# Tesseract_Motherboard.net
KiCad netlist of a schematic drawn in EasyEDA
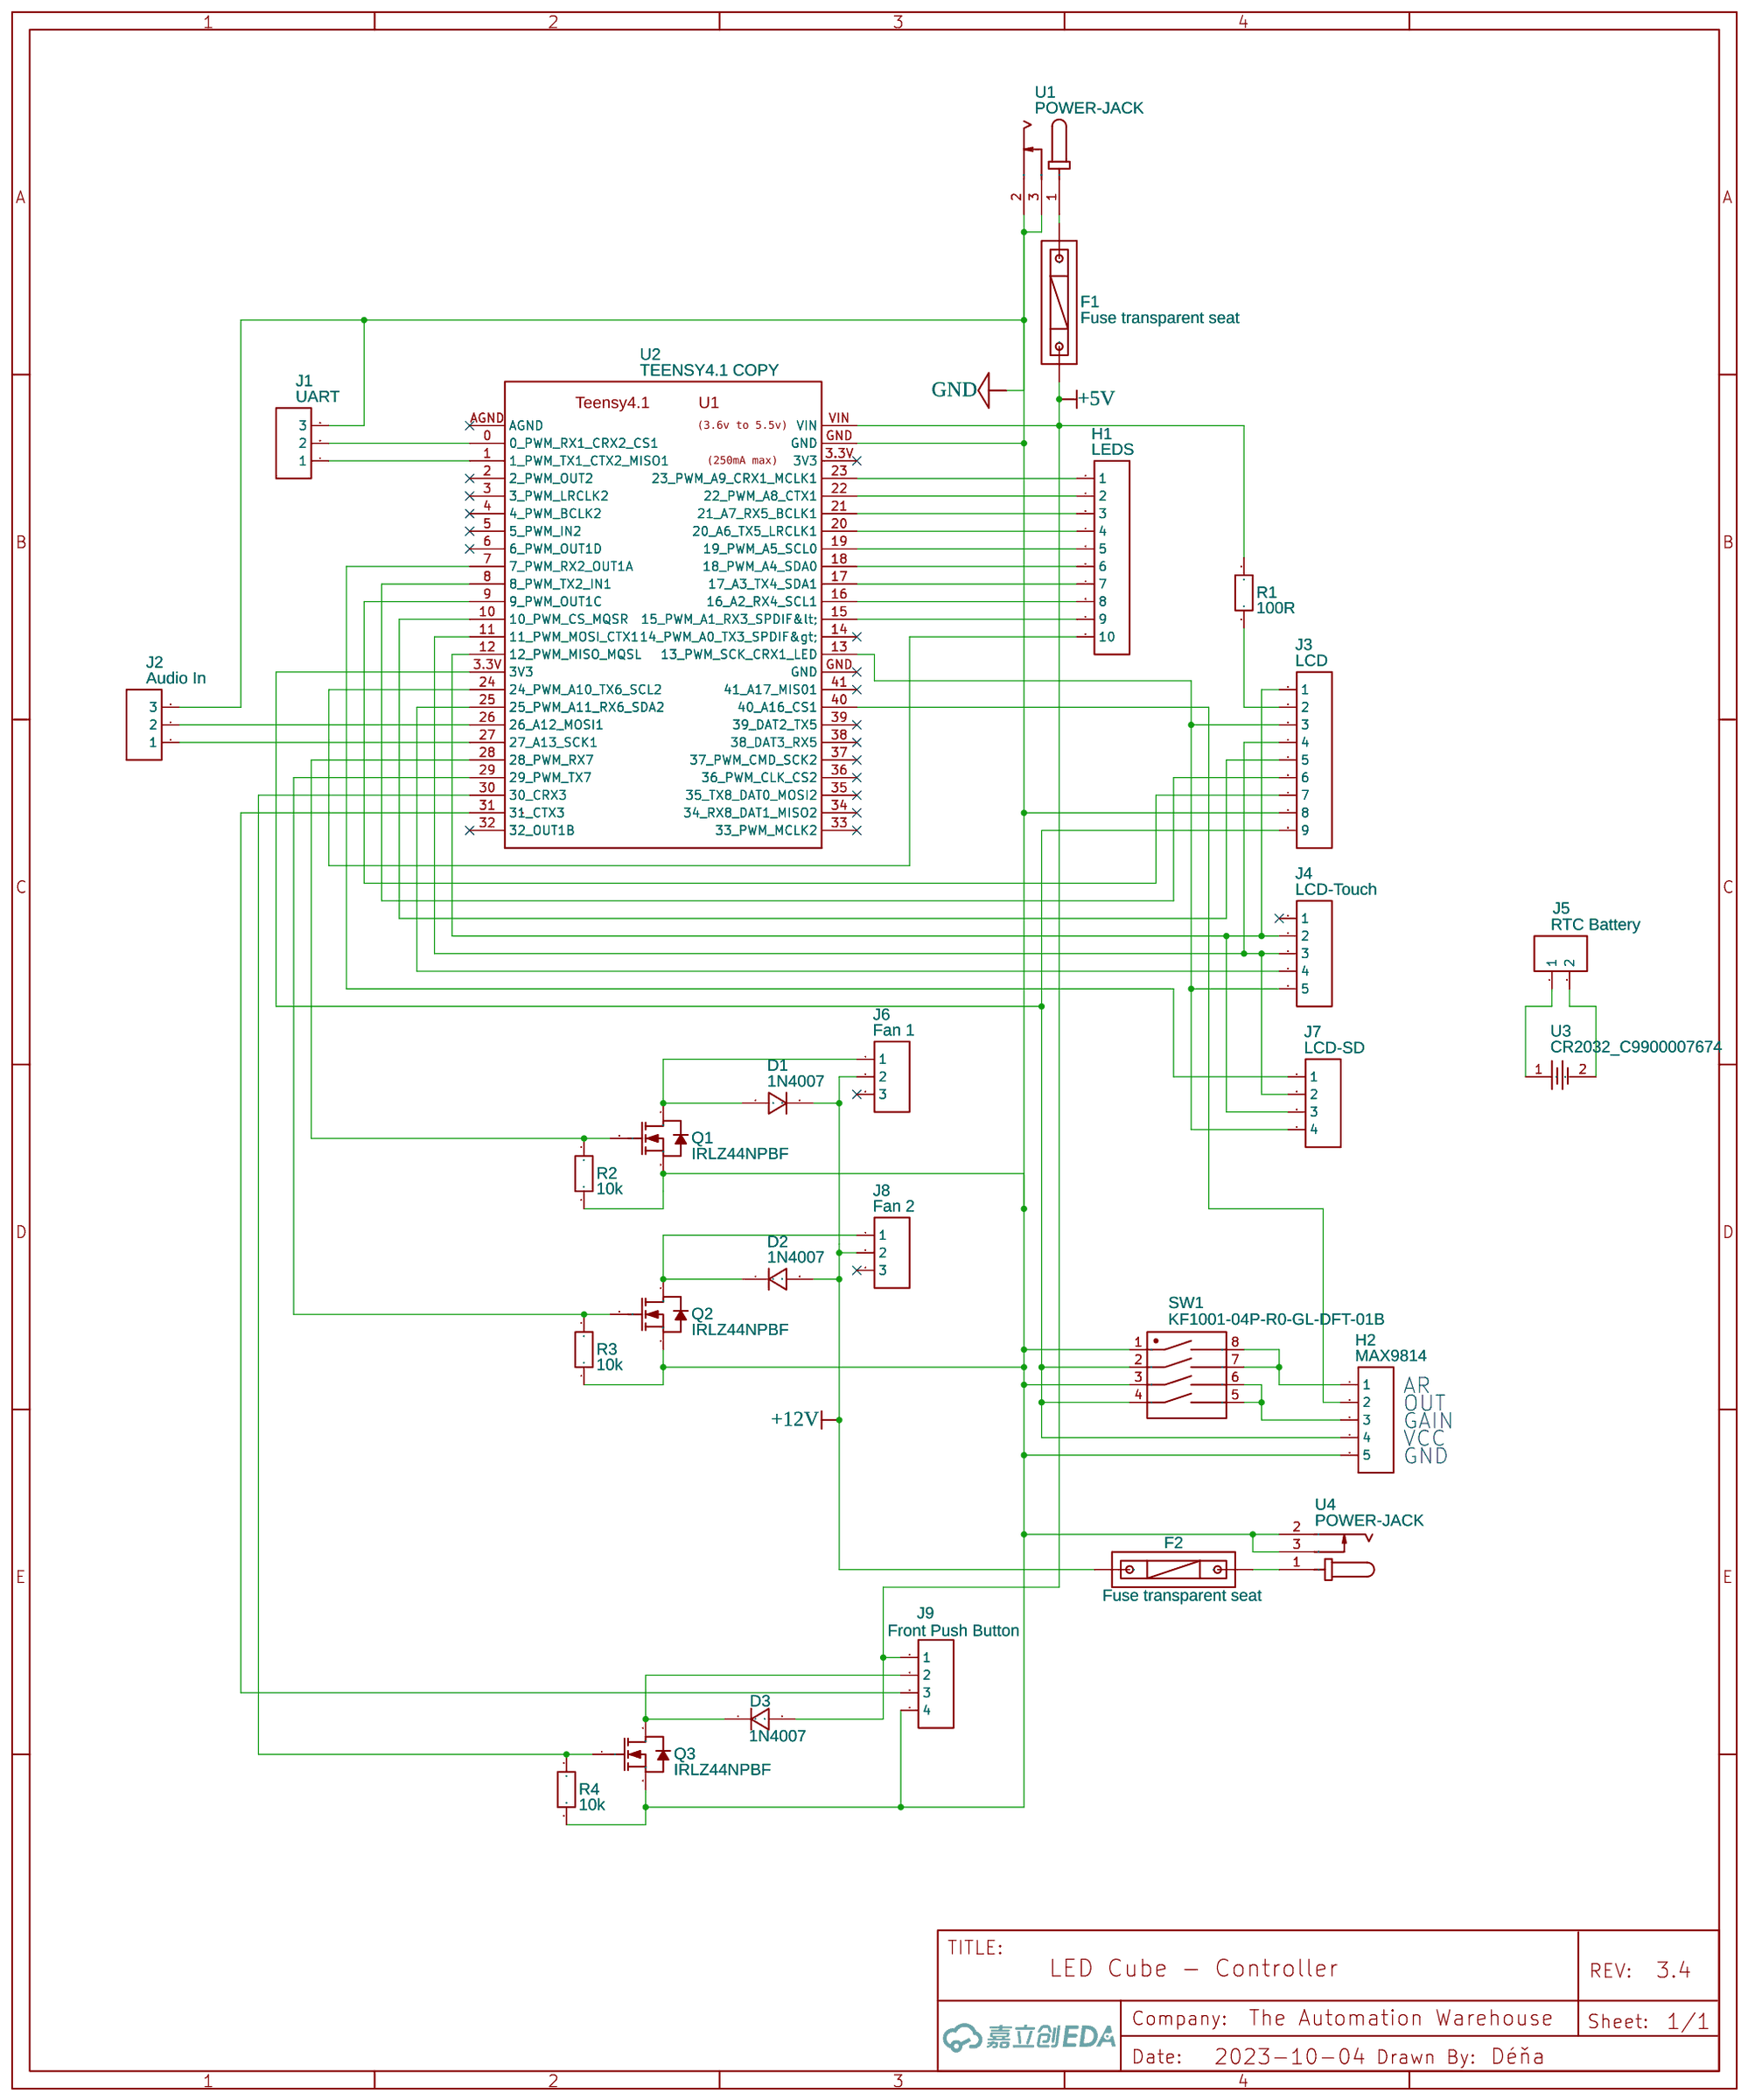
[diagram p0: schematic sheet]

(export (version "E")
  (design (tool "Eeschema 10.0.6"))
  (components
    (comp (ref "D1")
      (value "1N4007")
      (fields (field (name "BOM_Supplier Part") "C106903"))
      (libsource (lib "") (part "1N4007_1"))
    )
    (comp (ref "D2")
      (value "1N4007")
      (fields (field (name "BOM_Supplier Part") "C106903"))
      (libsource (lib "") (part "1N4007"))
    )
    (comp (ref "D3")
      (value "1N4007")
      (fields (field (name "BOM_Supplier Part") "C106903"))
      (libsource (lib "") (part "1N4007"))
    )
    (comp (ref "F1")
      (value "Fuse transparent seat")
      (fields (field (name "Manufacturer Part") "保险丝透明座") (field (name "Manufacturer") "xcfuse(旭程)"))
      (libsource (lib "") (part "Fuse transparent seat_1"))
    )
    (comp (ref "F2")
      (value "Fuse transparent seat")
      (fields (field (name "Manufacturer Part") "保险丝透明座") (field (name "Manufacturer") "xcfuse(旭程)"))
      (libsource (lib "") (part "Fuse transparent seat"))
    )
    (comp (ref "H1")
      (value "LEDS")
      (fields (field (name "BOM_Supplier Part") "C35445"))
      (libsource (lib "") (part "HDR-F-2.54_1x10"))
    )
    (comp (ref "H2")
      (value "MAX9814")
      (fields (field (name "BOM_Supplier Part") "C50950"))
      (libsource (lib "") (part "HDR-F-2.54_1x5"))
    )
    (comp (ref "J1")
      (value "UART")
      (fields (field (name "BOM_Supplier Part") "C180248"))
      (libsource (lib "") (part "HDR-M-2.54_1x3_1"))
    )
    (comp (ref "J2")
      (value "Audio In")
      (fields (field (name "BOM_Supplier Part") "C180248"))
      (libsource (lib "") (part "HDR-M-2.54_1x3_1"))
    )
    (comp (ref "J3")
      (value "LCD")
      (fields (field (name "BOM_Supplier Part") "C225484"))
      (libsource (lib "") (part "HDR-M-2.54_1x9"))
    )
    (comp (ref "J4")
      (value "LCD-Touch")
      (fields (field (name "BOM_Supplier Part") "C358687"))
      (libsource (lib "") (part "HDR-M-2.54_1x5"))
    )
    (comp (ref "J5")
      (value "RTC Battery")
      (fields (field (name "BOM_Supplier Part") "C124375"))
      (libsource (lib "") (part "HDR-M-2.54_1x2"))
    )
    (comp (ref "J6")
      (value "Fan 1")
      (fields (field (name "BOM_Supplier Part") "C180248"))
      (libsource (lib "") (part "HDR-M-2.54_1x3"))
    )
    (comp (ref "J7")
      (value "LCD-SD")
      (fields (field (name "BOM_Supplier Part") "C124378"))
      (libsource (lib "") (part "HDR-M-2.54_1x4"))
    )
    (comp (ref "J8")
      (value "Fan 2")
      (fields (field (name "BOM_Supplier Part") "C180248"))
      (libsource (lib "") (part "HDR-M-2.54_1x3"))
    )
    (comp (ref "J9")
      (value "Front Push Button")
      (fields (field (name "BOM_Supplier Part") "C124378"))
      (libsource (lib "") (part "HDR-M-2.54_1x4"))
    )
    (comp (ref "Q1")
      (value "IRLZ44NPBF")
      (fields (field (name "Manufacturer") "Infineon(英飞凌)"))
      (libsource (lib "") (part "IRLZ44NPBF"))
    )
    (comp (ref "Q2")
      (value "IRLZ44NPBF")
      (fields (field (name "Manufacturer") "Infineon(英飞凌)"))
      (libsource (lib "") (part "IRLZ44NPBF"))
    )
    (comp (ref "Q3")
      (value "IRLZ44NPBF")
      (fields (field (name "Manufacturer") "Infineon(英飞凌)"))
      (libsource (lib "") (part "IRLZ44NPBF"))
    )
    (comp (ref "R1") (value "100R") (libsource (lib "") (part "R_AXIAL-0.4_EU")))
    (comp (ref "R2") (value "10k") (libsource (lib "") (part "R_AXIAL-0.4_EU")))
    (comp (ref "R3") (value "10k") (libsource (lib "") (part "R_AXIAL-0.4_EU")))
    (comp (ref "R4") (value "10k") (libsource (lib "") (part "R_AXIAL-0.4_EU")))
    (comp (ref "SW1")
      (value "KF1001-04P-R0-GL-DFT-01B")
      (fields (field (name "Manufacturer") "凯峰"))
      (libsource (lib "") (part "KF1001-04P-R0-GL-DFT-01B"))
    )
    (comp (ref "U1")
      (value "POWER-JACK")
      (fields (field (name "BOM_Supplier Part") "C9900001795"))
      (libsource (lib "") (part "POWER-JACK"))
    )
    (comp (ref "U2")
      (value "TEENSY4.1 COPY")
      (fields (field (name "BOM_Manufacturer Part") "Teensy4.1"))
      (libsource (lib "") (part "TEENSY4.1 COPY"))
    )
    (comp (ref "U3")
      (value "CR2032_C9900007674")
      (fields (field (name "Manufacturer Part") "CR2032"))
      (libsource (lib "") (part "CR2032_C9900007674"))
    )
    (comp (ref "U4")
      (value "POWER-JACK")
      (fields (field (name "BOM_Supplier Part") "C9900001795"))
      (libsource (lib "") (part "POWER-JACK_1"))
    )
  )
  (nets
    (net (code "1") (name "+5V") (class "Default")
      (node (ref "D3") (pin "2") (pinfunction "2_2") (pintype "unspecified"))
      (node (ref "F1") (pin "1") (pinfunction "1_1") (pintype "unspecified"))
      (node (ref "J9") (pin "1") (pinfunction "1_1") (pintype "unspecified"))
      (node (ref "R1") (pin "2") (pinfunction "2_2") (pintype "unspecified"))
      (node (ref "U2") (pin "VIN") (pinfunction "VIN_VIN") (pintype "bidirectional"))
    )
    (net (code "2") (name "+12V") (class "Default")
      (node (ref "D1") (pin "1") (pinfunction "1_1") (pintype "unspecified"))
      (node (ref "D2") (pin "2") (pinfunction "2_2") (pintype "unspecified"))
      (node (ref "F2") (pin "1") (pinfunction "1_1") (pintype "unspecified"))
      (node (ref "J6") (pin "2") (pinfunction "2_2") (pintype "input"))
      (node (ref "J8") (pin "2") (pinfunction "2_2") (pintype "input"))
    )
    (net (code "3") (name "GND") (class "Default")
      (node (ref "H2") (pin "5") (pinfunction "5_5") (pintype "unspecified"))
      (node (ref "J1") (pin "3") (pinfunction "3_3") (pintype "input"))
      (node (ref "J2") (pin "3") (pinfunction "3_3") (pintype "input"))
      (node (ref "J3") (pin "8") (pinfunction "8_8") (pintype "unspecified"))
      (node (ref "J9") (pin "4") (pinfunction "4_4") (pintype "unspecified"))
      (node (ref "Q1") (pin "3") (pinfunction "S_3") (pintype "unspecified"))
      (node (ref "Q2") (pin "3") (pinfunction "S_3") (pintype "unspecified"))
      (node (ref "Q3") (pin "3") (pinfunction "S_3") (pintype "unspecified"))
      (node (ref "R2") (pin "1") (pinfunction "1_1") (pintype "unspecified"))
      (node (ref "R3") (pin "1") (pinfunction "1_1") (pintype "unspecified"))
      (node (ref "R4") (pin "1") (pinfunction "1_1") (pintype "unspecified"))
      (node (ref "SW1") (pin "1") (pinfunction "1_1") (pintype "unspecified"))
      (node (ref "SW1") (pin "3") (pinfunction "3_3") (pintype "unspecified"))
      (node (ref "U1") (pin "2") (pinfunction "2_2") (pintype "unspecified"))
      (node (ref "U1") (pin "3") (pinfunction "3_3") (pintype "unspecified"))
      (node (ref "U2") (pin "GND") (pinfunction "GND_GND") (pintype "bidirectional"))
      (node (ref "U4") (pin "2") (pinfunction "2_2") (pintype "unspecified"))
      (node (ref "U4") (pin "3") (pinfunction "3_3") (pintype "unspecified"))
    )
    (net (code "4") (name "Net-(F1-Pad2)") (class "Default")
      (node (ref "F1") (pin "2") (pinfunction "2_2") (pintype "unspecified"))
      (node (ref "U1") (pin "1") (pinfunction "1_1") (pintype "unspecified"))
    )
    (net (code "5") (name "Net-(F2-Pad2)") (class "Default")
      (node (ref "F2") (pin "2") (pinfunction "2_2") (pintype "unspecified"))
      (node (ref "U4") (pin "1") (pinfunction "1_1") (pintype "unspecified"))
    )
    (net (code "6") (name "Net-(J3-Pad2)") (class "Default")
      (node (ref "J3") (pin "2") (pinfunction "2_2") (pintype "unspecified"))
      (node (ref "R1") (pin "1") (pinfunction "1_1") (pintype "unspecified"))
    )
    (net (code "7") (name "Net-(J5-Pad1)") (class "Default")
      (node (ref "J5") (pin "1") (pinfunction "1_1") (pintype "unspecified"))
      (node (ref "U3") (pin "1") (pinfunction "1_1") (pintype "input"))
    )
    (net (code "8") (name "Net-(J5-Pad2)") (class "Default")
      (node (ref "J5") (pin "2") (pinfunction "2_2") (pintype "unspecified"))
      (node (ref "U3") (pin "2") (pinfunction "2_2") (pintype "input"))
    )
    (net (code "9") (name "Net-(Q1-D)") (class "Default")
      (node (ref "D1") (pin "2") (pinfunction "2_2") (pintype "unspecified"))
      (node (ref "J6") (pin "1") (pinfunction "1_1") (pintype "input"))
      (node (ref "Q1") (pin "2") (pinfunction "D_2") (pintype "unspecified"))
    )
    (net (code "10") (name "Net-(Q1-G)") (class "Default")
      (node (ref "Q1") (pin "1") (pinfunction "G_1") (pintype "unspecified"))
      (node (ref "R2") (pin "2") (pinfunction "2_2") (pintype "unspecified"))
      (node (ref "U2") (pin "28") (pinfunction "28_PWM_RX7_28") (pintype "bidirectional"))
    )
    (net (code "11") (name "Net-(Q2-D)") (class "Default")
      (node (ref "D2") (pin "1") (pinfunction "1_1") (pintype "unspecified"))
      (node (ref "J8") (pin "1") (pinfunction "1_1") (pintype "input"))
      (node (ref "Q2") (pin "2") (pinfunction "D_2") (pintype "unspecified"))
    )
    (net (code "12") (name "Net-(Q2-G)") (class "Default")
      (node (ref "Q2") (pin "1") (pinfunction "G_1") (pintype "unspecified"))
      (node (ref "R3") (pin "2") (pinfunction "2_2") (pintype "unspecified"))
      (node (ref "U2") (pin "29") (pinfunction "29_PWM_TX7_29") (pintype "bidirectional"))
    )
    (net (code "13") (name "Net-(Q3-D)") (class "Default")
      (node (ref "D3") (pin "1") (pinfunction "1_1") (pintype "unspecified"))
      (node (ref "J9") (pin "2") (pinfunction "2_2") (pintype "unspecified"))
      (node (ref "Q3") (pin "2") (pinfunction "D_2") (pintype "unspecified"))
    )
    (net (code "14") (name "Net-(Q3-G)") (class "Default")
      (node (ref "Q3") (pin "1") (pinfunction "G_1") (pintype "unspecified"))
      (node (ref "R4") (pin "2") (pinfunction "2_2") (pintype "unspecified"))
      (node (ref "U2") (pin "30") (pinfunction "30_CRX3_30") (pintype "bidirectional"))
    )
    (net (code "15") (name "Net-(SW1-6)") (class "Default")
      (node (ref "H2") (pin "3") (pinfunction "3_3") (pintype "unspecified"))
      (node (ref "SW1") (pin "5") (pinfunction "6_5") (pintype "unspecified"))
      (node (ref "SW1") (pin "6") (pinfunction "7_6") (pintype "unspecified"))
    )
    (net (code "16") (name "Net-(SW1-8)") (class "Default")
      (node (ref "H2") (pin "1") (pinfunction "1_1") (pintype "unspecified"))
      (node (ref "SW1") (pin "7") (pinfunction "8_7") (pintype "unspecified"))
      (node (ref "SW1") (pin "8") (pinfunction "9_8") (pintype "unspecified"))
    )
    (net (code "17") (name "Net-(U2-0_PWM_RX1_CRX2_CS1)") (class "Default")
      (node (ref "J1") (pin "2") (pinfunction "2_2") (pintype "input"))
      (node (ref "U2") (pin "0") (pinfunction "0_PWM_RX1_CRX2_CS1_0") (pintype "bidirectional"))
    )
    (net (code "18") (name "Net-(U2-1_PWM_TX1_CTX2_MISO1)") (class "Default")
      (node (ref "J1") (pin "1") (pinfunction "1_1") (pintype "input"))
      (node (ref "U2") (pin "1") (pinfunction "1_PWM_TX1_CTX2_MISO1_1") (pintype "bidirectional"))
    )
    (net (code "19") (name "Net-(U2-3V3)") (class "Default")
      (node (ref "H2") (pin "4") (pinfunction "4_4") (pintype "unspecified"))
      (node (ref "J3") (pin "9") (pinfunction "9_9") (pintype "unspecified"))
      (node (ref "SW1") (pin "2") (pinfunction "2_2") (pintype "unspecified"))
      (node (ref "SW1") (pin "4") (pinfunction "4_4") (pintype "unspecified"))
      (node (ref "U2") (pin "3.3V") (pinfunction "3V3_3.3V") (pintype "bidirectional"))
    )
    (net (code "20") (name "Net-(U2-7_PWM_RX2_OUT1A)") (class "Default")
      (node (ref "J7") (pin "1") (pinfunction "1_1") (pintype "unspecified"))
      (node (ref "U2") (pin "7") (pinfunction "7_PWM_RX2_OUT1A_7") (pintype "bidirectional"))
    )
    (net (code "21") (name "Net-(U2-8_PWM_TX2_IN1)") (class "Default")
      (node (ref "J3") (pin "6") (pinfunction "6_6") (pintype "unspecified"))
      (node (ref "U2") (pin "8") (pinfunction "8_PWM_TX2_IN1_8") (pintype "bidirectional"))
    )
    (net (code "22") (name "Net-(U2-9_PWM_OUT1C)") (class "Default")
      (node (ref "J3") (pin "7") (pinfunction "7_7") (pintype "unspecified"))
      (node (ref "U2") (pin "9") (pinfunction "9_PWM_OUT1C_9") (pintype "bidirectional"))
    )
    (net (code "23") (name "Net-(U2-10_PWM_CS_MQSR)") (class "Default")
      (node (ref "J3") (pin "5") (pinfunction "5_5") (pintype "unspecified"))
      (node (ref "U2") (pin "10") (pinfunction "10_PWM_CS_MQSR_10") (pintype "bidirectional"))
    )
    (net (code "24") (name "Net-(U2-11_PWM_MOSI_CTX1)") (class "Default")
      (node (ref "J3") (pin "4") (pinfunction "4_4") (pintype "unspecified"))
      (node (ref "J4") (pin "3") (pinfunction "3_3") (pintype "unspecified"))
      (node (ref "J7") (pin "2") (pinfunction "2_2") (pintype "unspecified"))
      (node (ref "U2") (pin "11") (pinfunction "11_PWM_MOSI_CTX1_11") (pintype "bidirectional"))
    )
    (net (code "25") (name "Net-(U2-12_PWM_MISO_MQSL)") (class "Default")
      (node (ref "J3") (pin "1") (pinfunction "1_1") (pintype "unspecified"))
      (node (ref "J4") (pin "2") (pinfunction "2_2") (pintype "unspecified"))
      (node (ref "J7") (pin "3") (pinfunction "3_3") (pintype "unspecified"))
      (node (ref "U2") (pin "12") (pinfunction "12_PWM_MISO_MQSL_12") (pintype "bidirectional"))
    )
    (net (code "26") (name "Net-(U2-13_PWM_SCK_CRX1_LED)") (class "Default")
      (node (ref "J3") (pin "3") (pinfunction "3_3") (pintype "unspecified"))
      (node (ref "J4") (pin "5") (pinfunction "5_5") (pintype "unspecified"))
      (node (ref "J7") (pin "4") (pinfunction "4_4") (pintype "unspecified"))
      (node (ref "U2") (pin "13") (pinfunction "13_PWM_SCK_CRX1_LED_13") (pintype "bidirectional"))
    )
    (net (code "27") (name "Net-(U2-15_PWM_A1_RX3_SPDIF&lt;)") (class "Default")
      (node (ref "H1") (pin "9") (pinfunction "9_9") (pintype "unspecified"))
      (node (ref "U2") (pin "15") (pinfunction "15_PWM_A1_RX3_SPDIF&lt;_15") (pintype "bidirectional"))
    )
    (net (code "28") (name "Net-(U2-16_A2_RX4_SCL1)") (class "Default")
      (node (ref "H1") (pin "8") (pinfunction "8_8") (pintype "unspecified"))
      (node (ref "U2") (pin "16") (pinfunction "16_A2_RX4_SCL1_16") (pintype "bidirectional"))
    )
    (net (code "29") (name "Net-(U2-17_A3_TX4_SDA1)") (class "Default")
      (node (ref "H1") (pin "7") (pinfunction "7_7") (pintype "unspecified"))
      (node (ref "U2") (pin "17") (pinfunction "17_A3_TX4_SDA1_17") (pintype "bidirectional"))
    )
    (net (code "30") (name "Net-(U2-18_PWM_A4_SDA0)") (class "Default")
      (node (ref "H1") (pin "6") (pinfunction "6_6") (pintype "unspecified"))
      (node (ref "U2") (pin "18") (pinfunction "18_PWM_A4_SDA0_18") (pintype "bidirectional"))
    )
    (net (code "31") (name "Net-(U2-19_PWM_A5_SCL0)") (class "Default")
      (node (ref "H1") (pin "5") (pinfunction "5_5") (pintype "unspecified"))
      (node (ref "U2") (pin "19") (pinfunction "19_PWM_A5_SCL0_19") (pintype "bidirectional"))
    )
    (net (code "32") (name "Net-(U2-20_A6_TX5_LRCLK1)") (class "Default")
      (node (ref "H1") (pin "4") (pinfunction "4_4") (pintype "unspecified"))
      (node (ref "U2") (pin "20") (pinfunction "20_A6_TX5_LRCLK1_20") (pintype "bidirectional"))
    )
    (net (code "33") (name "Net-(U2-21_A7_RX5_BCLK1)") (class "Default")
      (node (ref "H1") (pin "3") (pinfunction "3_3") (pintype "unspecified"))
      (node (ref "U2") (pin "21") (pinfunction "21_A7_RX5_BCLK1_21") (pintype "bidirectional"))
    )
    (net (code "34") (name "Net-(U2-22_PWM_A8_CTX1)") (class "Default")
      (node (ref "H1") (pin "2") (pinfunction "2_2") (pintype "unspecified"))
      (node (ref "U2") (pin "22") (pinfunction "22_PWM_A8_CTX1_22") (pintype "bidirectional"))
    )
    (net (code "35") (name "Net-(U2-23_PWM_A9_CRX1_MCLK1)") (class "Default")
      (node (ref "H1") (pin "1") (pinfunction "1_1") (pintype "unspecified"))
      (node (ref "U2") (pin "23") (pinfunction "23_PWM_A9_CRX1_MCLK1_23") (pintype "bidirectional"))
    )
    (net (code "36") (name "Net-(U2-24_PWM_A10_TX6_SCL2)") (class "Default")
      (node (ref "H1") (pin "10") (pinfunction "10_10") (pintype "unspecified"))
      (node (ref "U2") (pin "24") (pinfunction "24_PWM_A10_TX6_SCL2_24") (pintype "bidirectional"))
    )
    (net (code "37") (name "Net-(U2-25_PWM_A11_RX6_SDA2)") (class "Default")
      (node (ref "J4") (pin "4") (pinfunction "4_4") (pintype "unspecified"))
      (node (ref "U2") (pin "25") (pinfunction "25_PWM_A11_RX6_SDA2_25") (pintype "bidirectional"))
    )
    (net (code "38") (name "Net-(U2-26_A12_MOSI1)") (class "Default")
      (node (ref "J2") (pin "2") (pinfunction "2_2") (pintype "input"))
      (node (ref "U2") (pin "26") (pinfunction "26_A12_MOSI1_26") (pintype "bidirectional"))
    )
    (net (code "39") (name "Net-(U2-27_A13_SCK1)") (class "Default")
      (node (ref "J2") (pin "1") (pinfunction "1_1") (pintype "input"))
      (node (ref "U2") (pin "27") (pinfunction "27_A13_SCK1_27") (pintype "bidirectional"))
    )
    (net (code "40") (name "Net-(U2-31_CTX3)") (class "Default")
      (node (ref "J9") (pin "3") (pinfunction "3_3") (pintype "unspecified"))
      (node (ref "U2") (pin "31") (pinfunction "31_CTX3_31") (pintype "bidirectional"))
    )
    (net (code "41") (name "Net-(U2-40_A16_CS1)") (class "Default")
      (node (ref "H2") (pin "2") (pinfunction "2_2") (pintype "unspecified"))
      (node (ref "U2") (pin "40") (pinfunction "40_A16_CS1_40") (pintype "bidirectional"))
    )
    (net (code "42") (name "unconnected-(J4-Pad1)") (class "Default")
      (node (ref "J4") (pin "1") (pinfunction "1_1") (pintype "unspecified+no_connect"))
    )
    (net (code "43") (name "unconnected-(J6-Pad3)") (class "Default")
      (node (ref "J6") (pin "3") (pinfunction "3_3") (pintype "input+no_connect"))
    )
    (net (code "44") (name "unconnected-(J8-Pad3)") (class "Default")
      (node (ref "J8") (pin "3") (pinfunction "3_3") (pintype "input+no_connect"))
    )
    (net (code "45") (name "unconnected-(U2-2_PWM_OUT2-Pad2)") (class "Default")
      (node (ref "U2") (pin "2") (pinfunction "2_PWM_OUT2_2") (pintype "bidirectional+no_connect"))
    )
    (net (code "46") (name "unconnected-(U2-3V3-Pad3.3V)") (class "Default")
      (node (ref "U2") (pin "3.3V") (pinfunction "3V3_3.3V") (pintype "bidirectional+no_connect"))
    )
    (net (code "47") (name "unconnected-(U2-3_PWM_LRCLK2-Pad3)") (class "Default")
      (node (ref "U2") (pin "3") (pinfunction "3_PWM_LRCLK2_3") (pintype "bidirectional+no_connect"))
    )
    (net (code "48") (name "unconnected-(U2-4_PWM_BCLK2-Pad4)") (class "Default")
      (node (ref "U2") (pin "4") (pinfunction "4_PWM_BCLK2_4") (pintype "bidirectional+no_connect"))
    )
    (net (code "49") (name "unconnected-(U2-5_PWM_IN2-Pad5)") (class "Default")
      (node (ref "U2") (pin "5") (pinfunction "5_PWM_IN2_5") (pintype "bidirectional+no_connect"))
    )
    (net (code "50") (name "unconnected-(U2-6_PWM_OUT1D-Pad6)") (class "Default")
      (node (ref "U2") (pin "6") (pinfunction "6_PWM_OUT1D_6") (pintype "bidirectional+no_connect"))
    )
    (net (code "51") (name "unconnected-(U2-14_PWM_A0_TX3_SPDIF&gt;-Pad14)") (class "Default")
      (node (ref "U2") (pin "14") (pinfunction "14_PWM_A0_TX3_SPDIF&gt;_14") (pintype "bidirectional+no_connect"))
    )
    (net (code "52") (name "unconnected-(U2-32_OUT1B-Pad32)") (class "Default")
      (node (ref "U2") (pin "32") (pinfunction "32_OUT1B_32") (pintype "bidirectional+no_connect"))
    )
    (net (code "53") (name "unconnected-(U2-33_PWM_MCLK2-Pad33)") (class "Default")
      (node (ref "U2") (pin "33") (pinfunction "33_PWM_MCLK2_33") (pintype "bidirectional+no_connect"))
    )
    (net (code "54") (name "unconnected-(U2-34_RX8_DAT1_MISO2-Pad34)") (class "Default")
      (node (ref "U2") (pin "34") (pinfunction "34_RX8_DAT1_MISO2_34") (pintype "bidirectional+no_connect"))
    )
    (net (code "55") (name "unconnected-(U2-35_TX8_DAT0_MOSI2-Pad35)") (class "Default")
      (node (ref "U2") (pin "35") (pinfunction "35_TX8_DAT0_MOSI2_35") (pintype "bidirectional+no_connect"))
    )
    (net (code "56") (name "unconnected-(U2-36_PWM_CLK_CS2-Pad36)") (class "Default")
      (node (ref "U2") (pin "36") (pinfunction "36_PWM_CLK_CS2_36") (pintype "bidirectional+no_connect"))
    )
    (net (code "57") (name "unconnected-(U2-37_PWM_CMD_SCK2-Pad37)") (class "Default")
      (node (ref "U2") (pin "37") (pinfunction "37_PWM_CMD_SCK2_37") (pintype "bidirectional+no_connect"))
    )
    (net (code "58") (name "unconnected-(U2-38_DAT3_RX5-Pad38)") (class "Default")
      (node (ref "U2") (pin "38") (pinfunction "38_DAT3_RX5_38") (pintype "bidirectional+no_connect"))
    )
    (net (code "59") (name "unconnected-(U2-39_DAT2_TX5-Pad39)") (class "Default")
      (node (ref "U2") (pin "39") (pinfunction "39_DAT2_TX5_39") (pintype "bidirectional+no_connect"))
    )
    (net (code "60") (name "unconnected-(U2-41_A17_MIS01-Pad41)") (class "Default")
      (node (ref "U2") (pin "41") (pinfunction "41_A17_MIS01_41") (pintype "bidirectional+no_connect"))
    )
    (net (code "61") (name "unconnected-(U2-PadAGND)") (class "Default")
      (node (ref "U2") (pin "AGND") (pinfunction "AGND_AGND") (pintype "bidirectional+no_connect"))
    )
    (net (code "62") (name "unconnected-(U2-PadGND)") (class "Default")
      (node (ref "U2") (pin "GND") (pinfunction "GND_GND") (pintype "bidirectional+no_connect"))
    )
  )
)
